# Lesson1.net
KiCad netlist of a schematic drawn in Altium Designer
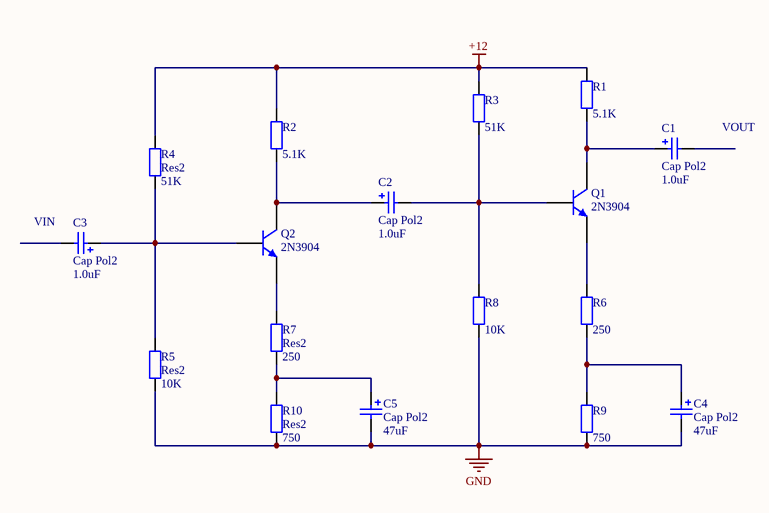
[diagram p0: Lesson1.SchDoc]

(export (version "E")
  (design (tool "Eeschema 10.0.6"))
  (components
    (comp (ref "C1")
      (value "Cap Pol2")
      (footprint "POLAR0.8")
      (description "Polarized Capacitor (Axial)")
      (fields (field (name "ALTIUM_VALUE") "1.0uF") (field (name "PUBLISHER") "Altium Limited"))
      (libsource (lib "Miscellaneous Devices") (part "Cap Pol2"))
    )
    (comp (ref "C2")
      (value "Cap Pol2")
      (footprint "POLAR0.8")
      (description "Polarized Capacitor (Axial)")
      (fields (field (name "ALTIUM_VALUE") "1.0uF") (field (name "PUBLISHER") "Altium Limited"))
      (libsource (lib "Miscellaneous Devices") (part "Cap Pol2"))
    )
    (comp (ref "C3")
      (value "Cap Pol2")
      (footprint "POLAR0.8")
      (description "Polarized Capacitor (Axial)")
      (fields (field (name "ALTIUM_VALUE") "1.0uF") (field (name "PUBLISHER") "Altium Limited"))
      (libsource (lib "Miscellaneous Devices") (part "Cap Pol2"))
    )
    (comp (ref "C4")
      (value "Cap Pol2")
      (footprint "POLAR0.8")
      (description "Polarized Capacitor (Axial)")
      (fields (field (name "ALTIUM_VALUE") "47uF") (field (name "PUBLISHER") "Altium Limited"))
      (libsource (lib "Miscellaneous Devices") (part "Cap Pol2"))
    )
    (comp (ref "C5")
      (value "Cap Pol2")
      (footprint "POLAR0.8")
      (description "Polarized Capacitor (Axial)")
      (fields (field (name "ALTIUM_VALUE") "47uF") (field (name "PUBLISHER") "Altium Limited"))
      (libsource (lib "Miscellaneous Devices") (part "Cap Pol2"))
    )
    (comp (ref "Q1")
      (value "2N3904")
      (footprint "TO-92A")
      (description "NPN General Purpose Amplifier")
      (fields (field (name "PUBLISHER") "Altium Limited"))
      (libsource (lib "Miscellaneous Devices") (part "2N3904"))
    )
    (comp (ref "Q2")
      (value "2N3904")
      (footprint "TO-92A")
      (description "NPN General Purpose Amplifier")
      (fields (field (name "PUBLISHER") "Altium Limited"))
      (libsource (lib "Miscellaneous Devices") (part "2N3904"))
    )
    (comp (ref "R1")
      (value "5.1K")
      (footprint "AXIAL-0.4")
      (description "Resistor")
      (fields (field (name "Comment") "Res2") (field (name "PUBLISHER") "Altium Limited"))
      (libsource (lib "Miscellaneous Devices") (part "Res2"))
    )
    (comp (ref "R2")
      (value "5.1K")
      (footprint "AXIAL-0.4")
      (description "Resistor")
      (fields (field (name "Comment") "Res2") (field (name "PUBLISHER") "Altium Limited"))
      (libsource (lib "Miscellaneous Devices") (part "Res2"))
    )
    (comp (ref "R3")
      (value "51K")
      (footprint "AXIAL-0.4")
      (description "Resistor")
      (fields (field (name "Comment") "Res2") (field (name "PUBLISHER") "Altium Limited"))
      (libsource (lib "Miscellaneous Devices") (part "Res2"))
    )
    (comp (ref "R4")
      (value "Res2")
      (footprint "AXIAL-0.4")
      (description "Resistor")
      (fields (field (name "ALTIUM_VALUE") "51K") (field (name "PUBLISHER") "Altium Limited"))
      (libsource (lib "Miscellaneous Devices") (part "Res2"))
    )
    (comp (ref "R5")
      (value "Res2")
      (footprint "AXIAL-0.4")
      (description "Resistor")
      (fields (field (name "ALTIUM_VALUE") "10K") (field (name "PUBLISHER") "Altium Limited"))
      (libsource (lib "Miscellaneous Devices") (part "Res2"))
    )
    (comp (ref "R6")
      (value "250")
      (footprint "AXIAL-0.4")
      (description "Resistor")
      (fields (field (name "Comment") "Res2") (field (name "PUBLISHER") "Altium Limited"))
      (libsource (lib "Miscellaneous Devices") (part "Res2"))
    )
    (comp (ref "R7")
      (value "Res2")
      (footprint "AXIAL-0.4")
      (description "Resistor")
      (fields (field (name "ALTIUM_VALUE") "250") (field (name "PUBLISHER") "Altium Limited"))
      (libsource (lib "Miscellaneous Devices") (part "Res2"))
    )
    (comp (ref "R8")
      (value "10K")
      (footprint "AXIAL-0.4")
      (description "Resistor")
      (fields (field (name "PUBLISHER") "Altium Limited"))
      (libsource (lib "Miscellaneous Devices") (part "Res2"))
    )
    (comp (ref "R9")
      (value "750")
      (footprint "AXIAL-0.4")
      (description "Resistor")
      (fields (field (name "Comment") "Res2") (field (name "PUBLISHER") "Altium Limited"))
      (libsource (lib "Miscellaneous Devices") (part "Res2"))
    )
    (comp (ref "R10")
      (value "Res2")
      (footprint "AXIAL-0.4")
      (description "Resistor")
      (fields (field (name "ALTIUM_VALUE") "750") (field (name "PUBLISHER") "Altium Limited"))
      (libsource (lib "Miscellaneous Devices") (part "Res2"))
    )
  )
  (nets
    (net (code "1") (name "+12") (class "Default")
      (node (ref "R1") (pin "2") (pinfunction "2_2") (pintype "passive"))
      (node (ref "R2") (pin "2") (pinfunction "2_2") (pintype "passive"))
      (node (ref "R3") (pin "2") (pinfunction "2_2") (pintype "passive"))
      (node (ref "R4") (pin "2") (pinfunction "2_2") (pintype "passive"))
    )
    (net (code "2") (name "GND") (class "Default")
      (node (ref "C4") (pin "2") (pinfunction "2_2") (pintype "passive"))
      (node (ref "C5") (pin "2") (pinfunction "2_2") (pintype "passive"))
      (node (ref "R10") (pin "1") (pinfunction "1_1") (pintype "passive"))
      (node (ref "R5") (pin "1") (pinfunction "1_1") (pintype "passive"))
      (node (ref "R8") (pin "1") (pinfunction "1_1") (pintype "passive"))
      (node (ref "R9") (pin "1") (pinfunction "1_1") (pintype "passive"))
    )
    (net (code "3") (name "Net-(C4-Pad1)") (class "Default")
      (node (ref "C4") (pin "1") (pinfunction "1_1") (pintype "passive"))
      (node (ref "R6") (pin "1") (pinfunction "1_1") (pintype "passive"))
      (node (ref "R9") (pin "2") (pinfunction "2_2") (pintype "passive"))
    )
    (net (code "4") (name "Net-(C5-Pad1)") (class "Default")
      (node (ref "C5") (pin "1") (pinfunction "1_1") (pintype "passive"))
      (node (ref "R10") (pin "2") (pinfunction "2_2") (pintype "passive"))
      (node (ref "R7") (pin "1") (pinfunction "1_1") (pintype "passive"))
    )
    (net (code "5") (name "Net-(Q1-B)") (class "Default")
      (node (ref "C2") (pin "2") (pinfunction "2_2") (pintype "passive"))
      (node (ref "Q1") (pin "2") (pinfunction "B_2") (pintype "passive"))
      (node (ref "R3") (pin "1") (pinfunction "1_1") (pintype "passive"))
      (node (ref "R8") (pin "2") (pinfunction "2_2") (pintype "passive"))
    )
    (net (code "6") (name "Net-(Q1-C)") (class "Default")
      (node (ref "C1") (pin "1") (pinfunction "1_1") (pintype "passive"))
      (node (ref "Q1") (pin "3") (pinfunction "C_3") (pintype "passive"))
      (node (ref "R1") (pin "1") (pinfunction "1_1") (pintype "passive"))
    )
    (net (code "7") (name "Net-(Q1-E)") (class "Default")
      (node (ref "Q1") (pin "1") (pinfunction "E_1") (pintype "passive"))
      (node (ref "R6") (pin "2") (pinfunction "2_2") (pintype "passive"))
    )
    (net (code "8") (name "Net-(Q2-B)") (class "Default")
      (node (ref "C3") (pin "1") (pinfunction "1_1") (pintype "passive"))
      (node (ref "Q2") (pin "2") (pinfunction "B_2") (pintype "passive"))
      (node (ref "R4") (pin "1") (pinfunction "1_1") (pintype "passive"))
      (node (ref "R5") (pin "2") (pinfunction "2_2") (pintype "passive"))
    )
    (net (code "9") (name "Net-(Q2-C)") (class "Default")
      (node (ref "C2") (pin "1") (pinfunction "1_1") (pintype "passive"))
      (node (ref "Q2") (pin "3") (pinfunction "C_3") (pintype "passive"))
      (node (ref "R2") (pin "1") (pinfunction "1_1") (pintype "passive"))
    )
    (net (code "10") (name "Net-(Q2-E)") (class "Default")
      (node (ref "Q2") (pin "1") (pinfunction "E_1") (pintype "passive"))
      (node (ref "R7") (pin "2") (pinfunction "2_2") (pintype "passive"))
    )
    (net (code "11") (name "unconnected-(C1-Pad2)") (class "Default")
      (node (ref "C1") (pin "2") (pinfunction "2_2") (pintype "passive"))
    )
    (net (code "12") (name "unconnected-(C3-Pad2)") (class "Default")
      (node (ref "C3") (pin "2") (pinfunction "2_2") (pintype "passive"))
    )
  )
)
